# Bluetooth.net
KiCad netlist of a schematic drawn in Altium Designer
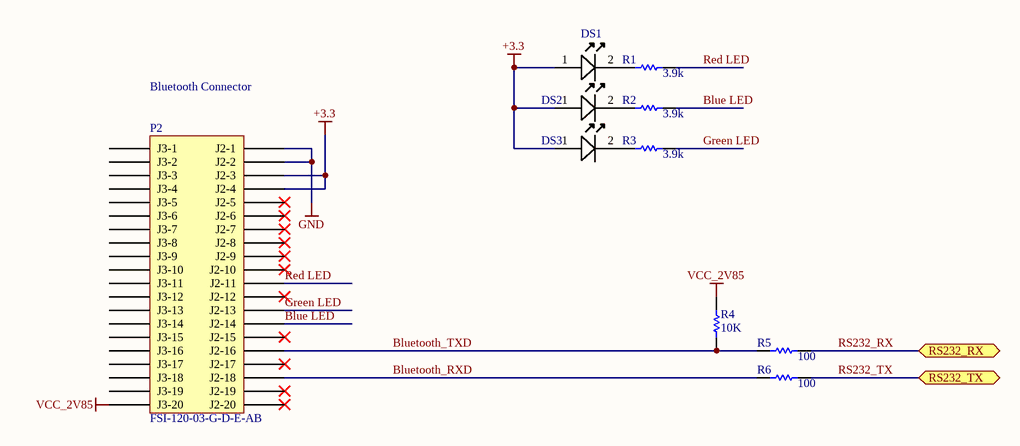
[diagram p0: Bluetooth.SchDoc]

(export (version "E")
  (design (tool "Eeschema 10.0.6"))
  (components
    (comp (ref "DS1")
      (value "Lite-On LTST-S220KGKT Green LED, 571 nm 2012 (0805) Side View, Rectangle Lens SMD package")
      (footprint "0805C_L")
      (fields
        (field (name "MANUFACTURER") "Vishay / Lite-On")
        (field (name "MANUFACTURER PART NUMBER") "LTST-S220KGKT")
      )
      (libsource (lib "*") (part "LED A/K"))
    )
    (comp (ref "DS2")
      (value "Lite-On LTST-S220KGKT Green LED, 571 nm 2012 (0805) Side View, Rectangle Lens SMD package")
      (footprint "0805C_L")
      (fields
        (field (name "MANUFACTURER") "Vishay / Lite-On")
        (field (name "MANUFACTURER PART NUMBER") "LTST-S220KGKT")
      )
      (libsource (lib "*") (part "LED A/K"))
    )
    (comp (ref "DS3")
      (value "Lite-On LTST-S220KGKT Green LED, 571 nm 2012 (0805) Side View, Rectangle Lens SMD package")
      (footprint "0805C_L")
      (fields
        (field (name "MANUFACTURER") "Vishay / Lite-On")
        (field (name "MANUFACTURER PART NUMBER") "LTST-S220KGKT")
      )
      (libsource (lib "*") (part "LED A/K"))
    )
    (comp (ref "P2")
      (value "FSI-120-03-G-D-E-AB")
      (footprint "FSI-120-03-G-D-E-AB")
      (fields (field (name "SUPPLIER PART NUMBER 1") "FSI-120-03-G-D-E-AB"))
      (libsource (lib "ZLS_Schematic_lib") (part "FSI-120-03-G-D-E-AB"))
    )
    (comp (ref "R1")
      (value "3.9k")
      (footprint "RESC0805(2012)_L")
      (description "2R55 0.125W 1% 0805 (2012 Metric)  SMD")
      (fields (field (name "TOLERANCE") "1 %") (field (name "POWER") "0.125 W"))
      (libsource (lib "Altium Content Vault") (part "CMP-1013-00215-1"))
    )
    (comp (ref "R2")
      (value "3.9k")
      (footprint "RESC0805(2012)_L")
      (description "2R55 0.125W 1% 0805 (2012 Metric)  SMD")
      (fields (field (name "TOLERANCE") "1 %") (field (name "POWER") "0.125 W"))
      (libsource (lib "Altium Content Vault") (part "CMP-1013-00215-1"))
    )
    (comp (ref "R3")
      (value "3.9k")
      (footprint "RESC0805(2012)_L")
      (description "2R55 0.125W 1% 0805 (2012 Metric)  SMD")
      (fields (field (name "TOLERANCE") "1 %") (field (name "POWER") "0.125 W"))
      (libsource (lib "Altium Content Vault") (part "CMP-1013-00215-1"))
    )
    (comp (ref "R4")
      (value "10K")
      (footprint "RESC0805(2012)_L")
      (description "2R55 0.125W 1% 0805 (2012 Metric)  SMD")
      (fields (field (name "TOLERANCE") "1 %") (field (name "POWER") "0.125 W"))
      (libsource (lib "Altium Content Vault") (part "CMP-1013-00215-1"))
    )
    (comp (ref "R5")
      (value "100")
      (footprint "RESC0805(2012)_L")
      (description "2R55 0.125W 1% 0805 (2012 Metric)  SMD")
      (fields (field (name "TOLERANCE") "1 %") (field (name "POWER") "0.125 W"))
      (libsource (lib "Altium Content Vault") (part "CMP-1013-00215-1"))
    )
    (comp (ref "R6")
      (value "100")
      (footprint "RESC0805(2012)_L")
      (description "2R55 0.125W 1% 0805 (2012 Metric)  SMD")
      (fields (field (name "TOLERANCE") "1 %") (field (name "POWER") "0.125 W"))
      (libsource (lib "Altium Content Vault") (part "CMP-1013-00215-1"))
    )
  )
  (nets
    (net (code "1") (name "+3.3") (class "Default")
      (node (ref "DS1") (pin "1") (pinfunction "A_1") (pintype "passive"))
      (node (ref "DS2") (pin "1") (pinfunction "A_1") (pintype "passive"))
      (node (ref "DS3") (pin "1") (pinfunction "A_1") (pintype "passive"))
      (node (ref "P2") (pin "J2-3") (pinfunction "J2-3_J2-3") (pintype "passive"))
      (node (ref "P2") (pin "J2-4") (pinfunction "J2-4_J2-4") (pintype "passive"))
    )
    (net (code "2") (name "/Blue LED") (class "Default")
      (node (ref "P2") (pin "J2-14") (pinfunction "J2-14_J2-14") (pintype "passive"))
      (node (ref "R2") (pin "1") (pinfunction "1_1") (pintype "passive"))
    )
    (net (code "3") (name "/Bluetooth_RXD") (class "Default")
      (node (ref "P2") (pin "J2-18") (pinfunction "J2-18_J2-18") (pintype "passive"))
      (node (ref "R6") (pin "2") (pinfunction "2_2") (pintype "passive"))
    )
    (net (code "4") (name "/Bluetooth_TXD") (class "Default")
      (node (ref "P2") (pin "J2-16") (pinfunction "J2-16_J2-16") (pintype "passive"))
      (node (ref "R4") (pin "2") (pinfunction "2_2") (pintype "passive"))
      (node (ref "R5") (pin "2") (pinfunction "2_2") (pintype "passive"))
    )
    (net (code "5") (name "/Green LED") (class "Default")
      (node (ref "P2") (pin "J2-13") (pinfunction "J2-13_J2-13") (pintype "passive"))
      (node (ref "R3") (pin "1") (pinfunction "1_1") (pintype "passive"))
    )
    (net (code "6") (name "/RS232_RX") (class "Default")
      (node (ref "R5") (pin "1") (pinfunction "1_1") (pintype "passive"))
    )
    (net (code "7") (name "/RS232_TX") (class "Default")
      (node (ref "R6") (pin "1") (pinfunction "1_1") (pintype "passive"))
    )
    (net (code "8") (name "/Red LED") (class "Default")
      (node (ref "P2") (pin "J2-11") (pinfunction "J2-11_J2-11") (pintype "passive"))
      (node (ref "R1") (pin "1") (pinfunction "1_1") (pintype "passive"))
    )
    (net (code "9") (name "GND") (class "Default")
      (node (ref "P2") (pin "J2-1") (pinfunction "J2-1_J2-1") (pintype "passive"))
      (node (ref "P2") (pin "J2-2") (pinfunction "J2-2_J2-2") (pintype "passive"))
    )
    (net (code "10") (name "Net-(DS1-K)") (class "Default")
      (node (ref "DS1") (pin "2") (pinfunction "K_2") (pintype "passive"))
      (node (ref "R1") (pin "2") (pinfunction "2_2") (pintype "passive"))
    )
    (net (code "11") (name "Net-(DS2-K)") (class "Default")
      (node (ref "DS2") (pin "2") (pinfunction "K_2") (pintype "passive"))
      (node (ref "R2") (pin "2") (pinfunction "2_2") (pintype "passive"))
    )
    (net (code "12") (name "Net-(DS3-K)") (class "Default")
      (node (ref "DS3") (pin "2") (pinfunction "K_2") (pintype "passive"))
      (node (ref "R3") (pin "2") (pinfunction "2_2") (pintype "passive"))
    )
    (net (code "13") (name "VCC_2V85") (class "Default")
      (node (ref "P2") (pin "J3-20") (pinfunction "J3-20_J3-20") (pintype "passive"))
      (node (ref "R4") (pin "1") (pinfunction "1_1") (pintype "passive"))
    )
    (net (code "14") (name "unconnected-(P2-PadJ2-5)") (class "Default")
      (node (ref "P2") (pin "J2-5") (pinfunction "J2-5_J2-5") (pintype "passive+no_connect"))
    )
    (net (code "15") (name "unconnected-(P2-PadJ2-6)") (class "Default")
      (node (ref "P2") (pin "J2-6") (pinfunction "J2-6_J2-6") (pintype "passive+no_connect"))
    )
    (net (code "16") (name "unconnected-(P2-PadJ2-7)") (class "Default")
      (node (ref "P2") (pin "J2-7") (pinfunction "J2-7_J2-7") (pintype "passive+no_connect"))
    )
    (net (code "17") (name "unconnected-(P2-PadJ2-8)") (class "Default")
      (node (ref "P2") (pin "J2-8") (pinfunction "J2-8_J2-8") (pintype "passive+no_connect"))
    )
    (net (code "18") (name "unconnected-(P2-PadJ2-9)") (class "Default")
      (node (ref "P2") (pin "J2-9") (pinfunction "J2-9_J2-9") (pintype "passive+no_connect"))
    )
    (net (code "19") (name "unconnected-(P2-PadJ2-10)") (class "Default")
      (node (ref "P2") (pin "J2-10") (pinfunction "J2-10_J2-10") (pintype "passive+no_connect"))
    )
    (net (code "20") (name "unconnected-(P2-PadJ2-12)") (class "Default")
      (node (ref "P2") (pin "J2-12") (pinfunction "J2-12_J2-12") (pintype "passive+no_connect"))
    )
    (net (code "21") (name "unconnected-(P2-PadJ2-15)") (class "Default")
      (node (ref "P2") (pin "J2-15") (pinfunction "J2-15_J2-15") (pintype "passive+no_connect"))
    )
    (net (code "22") (name "unconnected-(P2-PadJ2-17)") (class "Default")
      (node (ref "P2") (pin "J2-17") (pinfunction "J2-17_J2-17") (pintype "passive+no_connect"))
    )
    (net (code "23") (name "unconnected-(P2-PadJ2-19)") (class "Default")
      (node (ref "P2") (pin "J2-19") (pinfunction "J2-19_J2-19") (pintype "passive+no_connect"))
    )
    (net (code "24") (name "unconnected-(P2-PadJ2-20)") (class "Default")
      (node (ref "P2") (pin "J2-20") (pinfunction "J2-20_J2-20") (pintype "passive+no_connect"))
    )
    (net (code "25") (name "unconnected-(P2-PadJ3-1)") (class "Default")
      (node (ref "P2") (pin "J3-1") (pinfunction "J3-1_J3-1") (pintype "passive"))
    )
    (net (code "26") (name "unconnected-(P2-PadJ3-2)") (class "Default")
      (node (ref "P2") (pin "J3-2") (pinfunction "J3-2_J3-2") (pintype "passive"))
    )
    (net (code "27") (name "unconnected-(P2-PadJ3-3)") (class "Default")
      (node (ref "P2") (pin "J3-3") (pinfunction "J3-3_J3-3") (pintype "passive"))
    )
    (net (code "28") (name "unconnected-(P2-PadJ3-4)") (class "Default")
      (node (ref "P2") (pin "J3-4") (pinfunction "J3-4_J3-4") (pintype "passive"))
    )
    (net (code "29") (name "unconnected-(P2-PadJ3-5)") (class "Default")
      (node (ref "P2") (pin "J3-5") (pinfunction "J3-5_J3-5") (pintype "passive"))
    )
    (net (code "30") (name "unconnected-(P2-PadJ3-6)") (class "Default")
      (node (ref "P2") (pin "J3-6") (pinfunction "J3-6_J3-6") (pintype "passive"))
    )
    (net (code "31") (name "unconnected-(P2-PadJ3-7)") (class "Default")
      (node (ref "P2") (pin "J3-7") (pinfunction "J3-7_J3-7") (pintype "passive"))
    )
    (net (code "32") (name "unconnected-(P2-PadJ3-8)") (class "Default")
      (node (ref "P2") (pin "J3-8") (pinfunction "J3-8_J3-8") (pintype "passive"))
    )
    (net (code "33") (name "unconnected-(P2-PadJ3-9)") (class "Default")
      (node (ref "P2") (pin "J3-9") (pinfunction "J3-9_J3-9") (pintype "passive"))
    )
    (net (code "34") (name "unconnected-(P2-PadJ3-10)") (class "Default")
      (node (ref "P2") (pin "J3-10") (pinfunction "J3-10_J3-10") (pintype "passive"))
    )
    (net (code "35") (name "unconnected-(P2-PadJ3-11)") (class "Default")
      (node (ref "P2") (pin "J3-11") (pinfunction "J3-11_J3-11") (pintype "passive"))
    )
    (net (code "36") (name "unconnected-(P2-PadJ3-12)") (class "Default")
      (node (ref "P2") (pin "J3-12") (pinfunction "J3-12_J3-12") (pintype "passive"))
    )
    (net (code "37") (name "unconnected-(P2-PadJ3-13)") (class "Default")
      (node (ref "P2") (pin "J3-13") (pinfunction "J3-13_J3-13") (pintype "passive"))
    )
    (net (code "38") (name "unconnected-(P2-PadJ3-14)") (class "Default")
      (node (ref "P2") (pin "J3-14") (pinfunction "J3-14_J3-14") (pintype "passive"))
    )
    (net (code "39") (name "unconnected-(P2-PadJ3-15)") (class "Default")
      (node (ref "P2") (pin "J3-15") (pinfunction "J3-15_J3-15") (pintype "passive"))
    )
    (net (code "40") (name "unconnected-(P2-PadJ3-16)") (class "Default")
      (node (ref "P2") (pin "J3-16") (pinfunction "J3-16_J3-16") (pintype "passive"))
    )
    (net (code "41") (name "unconnected-(P2-PadJ3-17)") (class "Default")
      (node (ref "P2") (pin "J3-17") (pinfunction "J3-17_J3-17") (pintype "passive"))
    )
    (net (code "42") (name "unconnected-(P2-PadJ3-18)") (class "Default")
      (node (ref "P2") (pin "J3-18") (pinfunction "J3-18_J3-18") (pintype "passive"))
    )
    (net (code "43") (name "unconnected-(P2-PadJ3-19)") (class "Default")
      (node (ref "P2") (pin "J3-19") (pinfunction "J3-19_J3-19") (pintype "passive"))
    )
  )
)
